# tvbgonesmd4led.net
KiCad netlist of a schematic drawn in EAGLE
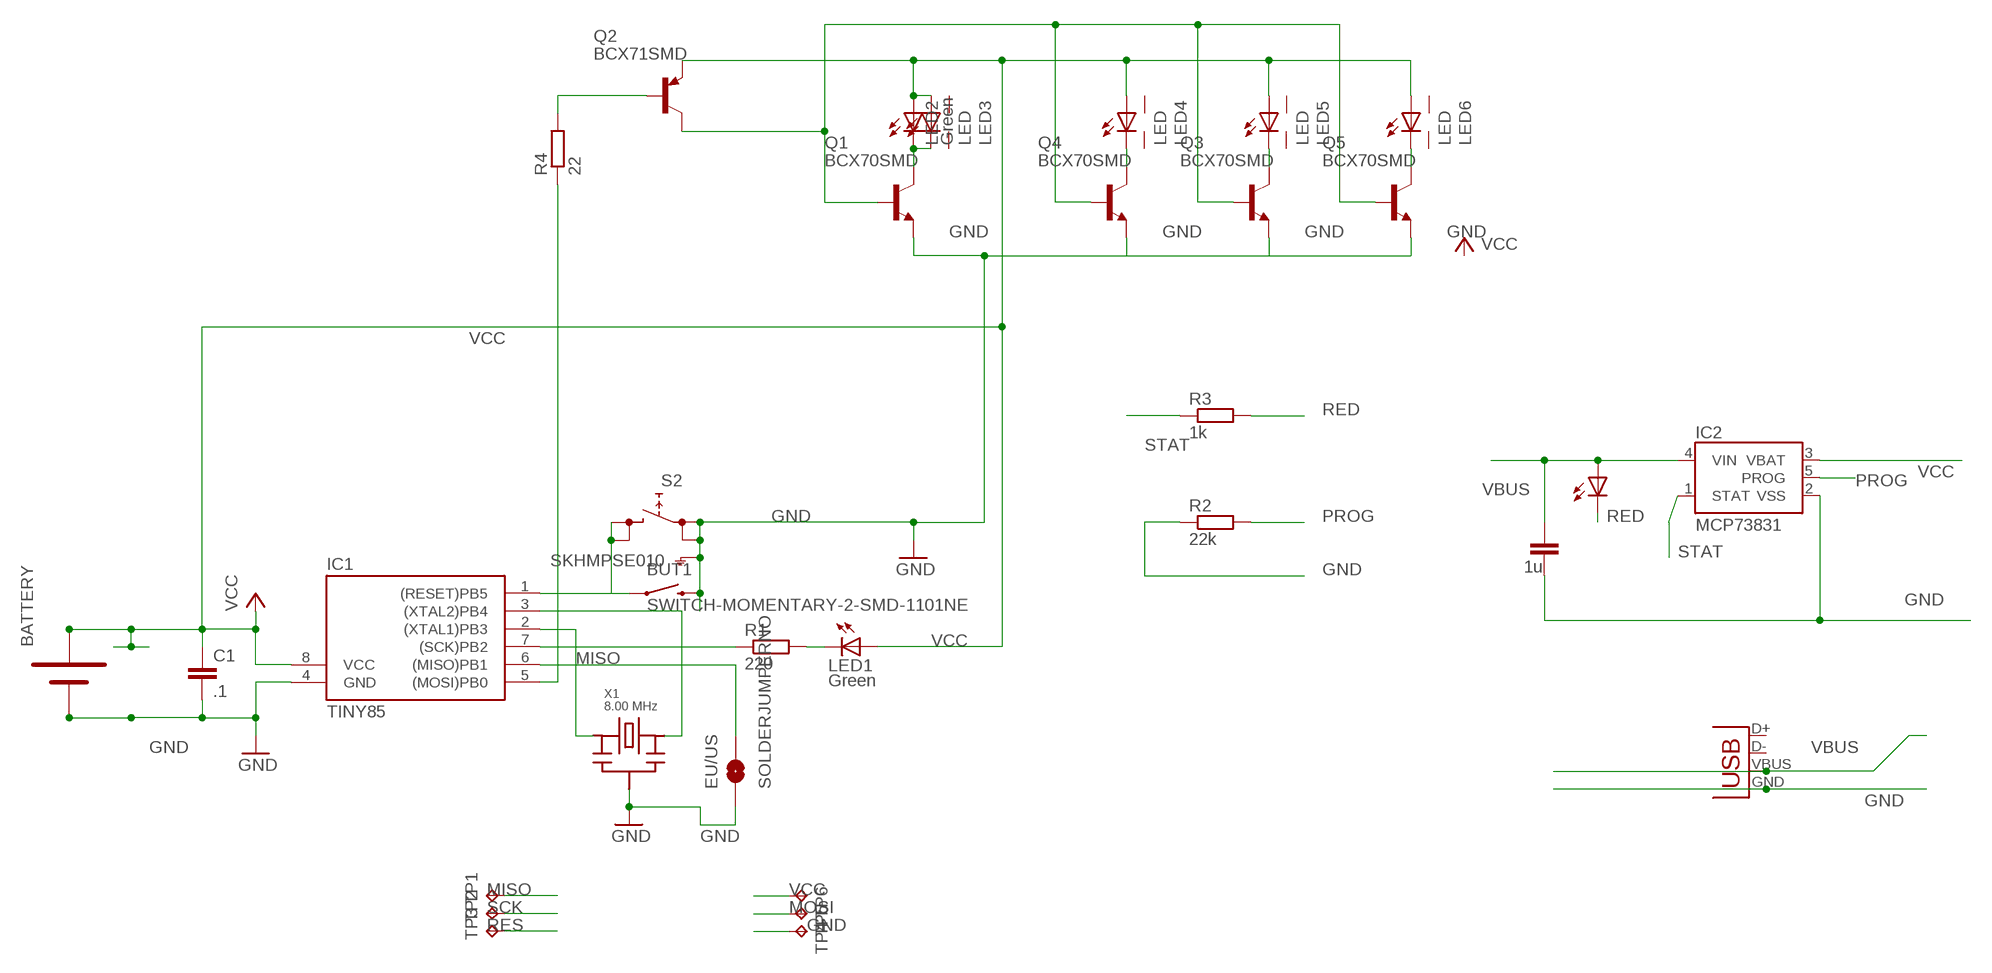
[diagram p0: schematic, sheet 1]

(export (version "E")
  (design (tool "Eeschema 10.0.6"))
  (components
    (comp (ref "BATTERY")
      (value "BATTERY-1XAA20MM")
      (footprint "eagle-import:BATTCOM_20MM_PTH")
      (libsource (lib "eagle-import") (part "BATTERY-1XAA20MM"))
    )
    (comp (ref "BUT1")
      (value "SWITCH-MOMENTARY-2-SMD-1101NE")
      (footprint "eagle-import:TACTILE-SWITCH-1101NE")
      (libsource (lib "eagle-import") (part "SWITCH-MOMENTARY-2-SMD-1101NE"))
    )
    (comp (ref "C1")
      (value ".1")
      (footprint "eagle-import:C0603")
      (libsource (lib "eagle-import") (part "C-EUC0603"))
    )
    (comp (ref "C2")
      (value "1u")
      (footprint "eagle-import:C0603")
      (libsource (lib "eagle-import") (part "resistor_C-EUC0603"))
    )
    (comp (ref "CHG")
      (value "0805")
      (footprint "eagle-import:CHIPLED_0603")
      (libsource (lib "eagle-import") (part "LEDCHIPLED_0603"))
    )
    (comp (ref "EU/US")
      (value "SOLDERJUMPERNO")
      (footprint "eagle-import:SJ_2S-NO")
      (libsource (lib "eagle-import") (part "SOLDERJUMPERNO"))
    )
    (comp (ref "IC1")
      (value "TINY85")
      (footprint "eagle-import:SOIC8")
      (libsource (lib "eagle-import") (part "TINY12S"))
    )
    (comp (ref "IC2")
      (value "MCP73831")
      (footprint "eagle-import:SOT23-5")
      (libsource (lib "eagle-import") (part "MCP73831"))
    )
    (comp (ref "LED1")
      (value "Green")
      (footprint "eagle-import:CHIPLED_0603")
      (libsource (lib "eagle-import") (part "LEDCHIPLED_0603"))
    )
    (comp (ref "LED2")
      (value "Green")
      (footprint "eagle-import:CHIPLED_0805")
      (libsource (lib "eagle-import") (part "LEDCHIPLED_0805"))
    )
    (comp (ref "LED3")
      (value "LED")
      (footprint "eagle-import:5MM-SIDE")
      (libsource (lib "eagle-import") (part "tvbgone_LED"))
    )
    (comp (ref "LED4")
      (value "LED")
      (footprint "eagle-import:5MM-SIDE")
      (libsource (lib "eagle-import") (part "tvbgone_LED"))
    )
    (comp (ref "LED5")
      (value "LED")
      (footprint "eagle-import:5MM-SIDE")
      (libsource (lib "eagle-import") (part "tvbgone_LED"))
    )
    (comp (ref "LED6")
      (value "LED")
      (footprint "eagle-import:5MM-SIDE")
      (libsource (lib "eagle-import") (part "tvbgone_LED"))
    )
    (comp (ref "Q1")
      (value "BCX70SMD")
      (footprint "eagle-import:SOT23")
      (libsource (lib "eagle-import") (part "BCX70SMD"))
    )
    (comp (ref "Q2")
      (value "BCX71SMD")
      (footprint "eagle-import:SOT23")
      (libsource (lib "eagle-import") (part "BCX71SMD"))
    )
    (comp (ref "Q3")
      (value "BCX70SMD")
      (footprint "eagle-import:SOT23")
      (libsource (lib "eagle-import") (part "BCX70SMD"))
    )
    (comp (ref "Q4")
      (value "BCX70SMD")
      (footprint "eagle-import:SOT23")
      (libsource (lib "eagle-import") (part "BCX70SMD"))
    )
    (comp (ref "Q5")
      (value "BCX70SMD")
      (footprint "eagle-import:SOT23")
      (libsource (lib "eagle-import") (part "BCX70SMD"))
    )
    (comp (ref "R1")
      (value "220")
      (footprint "eagle-import:R0603")
      (libsource (lib "eagle-import") (part "R-EU_R0603"))
    )
    (comp (ref "R2")
      (value "22k")
      (footprint "eagle-import:R0603")
      (libsource (lib "eagle-import") (part "R-EU_R0603"))
    )
    (comp (ref "R3")
      (value "1k")
      (footprint "eagle-import:R0603")
      (libsource (lib "eagle-import") (part "R-EU_R0603"))
    )
    (comp (ref "R4")
      (value "22")
      (footprint "eagle-import:R0603")
      (libsource (lib "eagle-import") (part "R-EU_R0603"))
    )
    (comp (ref "S2")
      (value "SKHMPSE010")
      (footprint "eagle-import:SKHMPXE010")
      (libsource (lib "eagle-import") (part "SKHMPE010S"))
    )
    (comp (ref "TP1")
      (value "TPB1,27")
      (footprint "eagle-import:B1,27")
      (libsource (lib "eagle-import") (part "TPB1,27"))
    )
    (comp (ref "TP2")
      (value "TPB1,27")
      (footprint "eagle-import:B1,27")
      (libsource (lib "eagle-import") (part "TPB1,27"))
    )
    (comp (ref "TP3")
      (value "TPB1,27")
      (footprint "eagle-import:B1,27")
      (libsource (lib "eagle-import") (part "TPB1,27"))
    )
    (comp (ref "TP4")
      (value "TPB1,27")
      (footprint "eagle-import:B1,27")
      (libsource (lib "eagle-import") (part "TPB1,27"))
    )
    (comp (ref "TP5")
      (value "TPB1,27")
      (footprint "eagle-import:B1,27")
      (libsource (lib "eagle-import") (part "TPB1,27"))
    )
    (comp (ref "TP6")
      (value "TPB1,27")
      (footprint "eagle-import:B1,27")
      (libsource (lib "eagle-import") (part "TPB1,27"))
    )
    (comp (ref "X1")
      (value "8.00 MHz")
      (footprint "eagle-import:AWSCR")
      (libsource (lib "eagle-import") (part "AWSCR-MT"))
    )
    (comp (ref "X6")
      (value "USB-MICROB")
      (footprint "eagle-import:USB-MICROB")
      (libsource (lib "eagle-import") (part "USB-MICROB"))
    )
  )
  (nets
    (net (code "1") (name "/MISO") (class "Default")
      (node (ref "EU/US") (pin "2") (pinfunction "2_2") (pintype "passive"))
      (node (ref "IC1") (pin "6") (pinfunction "(MISO)PB1_6") (pintype "bidirectional"))
      (node (ref "TP1") (pin "TP") (pinfunction "TP_TP") (pintype "input"))
    )
    (net (code "2") (name "/MOSI") (class "Default")
      (node (ref "IC1") (pin "5") (pinfunction "(MOSI)PB0_5") (pintype "bidirectional"))
      (node (ref "R4") (pin "1") (pinfunction "1_1") (pintype "passive"))
      (node (ref "TP5") (pin "TP") (pinfunction "TP_TP") (pintype "input"))
    )
    (net (code "3") (name "/PROG") (class "Default")
      (node (ref "IC2") (pin "5") (pinfunction "PROG_5") (pintype "input"))
      (node (ref "R2") (pin "2") (pinfunction "2_2") (pintype "passive"))
    )
    (net (code "4") (name "/RED") (class "Default")
      (node (ref "CHG") (pin "C") (pinfunction "C_C") (pintype "passive"))
      (node (ref "R3") (pin "2") (pinfunction "2_2") (pintype "passive"))
    )
    (net (code "5") (name "/RES") (class "Default")
      (node (ref "BUT1") (pin "P$1") (pinfunction "1_P$1") (pintype "passive"))
      (node (ref "IC1") (pin "1") (pinfunction "(RESET)PB5_1") (pintype "bidirectional"))
      (node (ref "S2") (pin "3") (pinfunction "2.1_3") (pintype "passive"))
      (node (ref "S2") (pin "4") (pinfunction "2.2_4") (pintype "passive"))
      (node (ref "TP3") (pin "TP") (pinfunction "TP_TP") (pintype "input"))
    )
    (net (code "6") (name "/SCK") (class "Default")
      (node (ref "IC1") (pin "7") (pinfunction "(SCK)PB2_7") (pintype "bidirectional"))
      (node (ref "R1") (pin "1") (pinfunction "1_1") (pintype "passive"))
      (node (ref "TP2") (pin "TP") (pinfunction "TP_TP") (pintype "input"))
    )
    (net (code "7") (name "/STAT") (class "Default")
      (node (ref "IC2") (pin "1") (pinfunction "STAT_1") (pintype "output"))
      (node (ref "R3") (pin "1") (pinfunction "1_1") (pintype "passive"))
    )
    (net (code "8") (name "/VBUS") (class "Default")
      (node (ref "C2") (pin "1") (pinfunction "1_1") (pintype "passive"))
      (node (ref "CHG") (pin "A") (pinfunction "A_A") (pintype "passive"))
      (node (ref "IC2") (pin "4") (pinfunction "VIN_4") (pintype "power_in"))
      (node (ref "X6") (pin "VBUS") (pinfunction "VBUS_VBUS") (pintype "bidirectional"))
    )
    (net (code "9") (name "GND") (class "Default")
      (node (ref "BATTERY") (pin "-") (pinfunction "-_-") (pintype "bidirectional"))
      (node (ref "BUT1") (pin "P$2") (pinfunction "2_P$2") (pintype "passive"))
      (node (ref "C1") (pin "2") (pinfunction "2_2") (pintype "passive"))
      (node (ref "C2") (pin "2") (pinfunction "2_2") (pintype "passive"))
      (node (ref "EU/US") (pin "1") (pinfunction "1_1") (pintype "passive"))
      (node (ref "IC1") (pin "4") (pinfunction "GND_4") (pintype "power_in"))
      (node (ref "IC2") (pin "2") (pinfunction "VSS_2") (pintype "power_in"))
      (node (ref "Q1") (pin "2") (pinfunction "E_2") (pintype "passive"))
      (node (ref "Q3") (pin "2") (pinfunction "E_2") (pintype "passive"))
      (node (ref "Q4") (pin "2") (pinfunction "E_2") (pintype "passive"))
      (node (ref "Q5") (pin "2") (pinfunction "E_2") (pintype "passive"))
      (node (ref "R2") (pin "1") (pinfunction "1_1") (pintype "passive"))
      (node (ref "S2") (pin "1") (pinfunction "1.1_1") (pintype "passive"))
      (node (ref "S2") (pin "2") (pinfunction "1.2_2") (pintype "passive"))
      (node (ref "S2") (pin "5") (pinfunction "SH_5") (pintype "passive"))
      (node (ref "TP4") (pin "TP") (pinfunction "TP_TP") (pintype "input"))
      (node (ref "X1") (pin "P$2") (pinfunction "GND_P$2") (pintype "passive"))
      (node (ref "X6") (pin "GND") (pinfunction "GND_GND") (pintype "bidirectional"))
    )
    (net (code "10") (name "Net-(IC1-(XTAL1)PB3)") (class "Default")
      (node (ref "IC1") (pin "2") (pinfunction "(XTAL1)PB3_2") (pintype "bidirectional"))
      (node (ref "X1") (pin "P$1") (pinfunction "P$1_P$1") (pintype "passive"))
    )
    (net (code "11") (name "Net-(IC1-(XTAL2)PB4)") (class "Default")
      (node (ref "IC1") (pin "3") (pinfunction "(XTAL2)PB4_3") (pintype "bidirectional"))
      (node (ref "X1") (pin "P$3") (pinfunction "P$2_P$3") (pintype "passive"))
    )
    (net (code "12") (name "Net-(LED1-PadC)") (class "Default")
      (node (ref "LED1") (pin "C") (pinfunction "C_C") (pintype "passive"))
      (node (ref "R1") (pin "2") (pinfunction "2_2") (pintype "passive"))
    )
    (net (code "13") (name "Net-(LED3-C)") (class "Default")
      (node (ref "LED2") (pin "C") (pinfunction "C_C") (pintype "passive"))
      (node (ref "LED3") (pin "K") (pinfunction "C_K") (pintype "passive"))
      (node (ref "Q1") (pin "3") (pinfunction "C_3") (pintype "passive"))
    )
    (net (code "14") (name "Net-(LED4-C)") (class "Default")
      (node (ref "LED4") (pin "K") (pinfunction "C_K") (pintype "passive"))
      (node (ref "Q4") (pin "3") (pinfunction "C_3") (pintype "passive"))
    )
    (net (code "15") (name "Net-(LED5-C)") (class "Default")
      (node (ref "LED5") (pin "K") (pinfunction "C_K") (pintype "passive"))
      (node (ref "Q3") (pin "3") (pinfunction "C_3") (pintype "passive"))
    )
    (net (code "16") (name "Net-(LED6-C)") (class "Default")
      (node (ref "LED6") (pin "K") (pinfunction "C_K") (pintype "passive"))
      (node (ref "Q5") (pin "3") (pinfunction "C_3") (pintype "passive"))
    )
    (net (code "17") (name "Net-(Q1-B)") (class "Default")
      (node (ref "Q1") (pin "1") (pinfunction "B_1") (pintype "passive"))
      (node (ref "Q2") (pin "3") (pinfunction "C_3") (pintype "passive"))
      (node (ref "Q3") (pin "1") (pinfunction "B_1") (pintype "passive"))
      (node (ref "Q4") (pin "1") (pinfunction "B_1") (pintype "passive"))
      (node (ref "Q5") (pin "1") (pinfunction "B_1") (pintype "passive"))
    )
    (net (code "18") (name "Net-(Q2-B)") (class "Default")
      (node (ref "Q2") (pin "1") (pinfunction "B_1") (pintype "passive"))
      (node (ref "R4") (pin "2") (pinfunction "2_2") (pintype "passive"))
    )
    (net (code "19") (name "VCC") (class "Default")
      (node (ref "BATTERY") (pin "+") (pinfunction "+_+") (pintype "bidirectional"))
      (node (ref "C1") (pin "1") (pinfunction "1_1") (pintype "passive"))
      (node (ref "IC1") (pin "8") (pinfunction "VCC_8") (pintype "power_in"))
      (node (ref "IC2") (pin "3") (pinfunction "VBAT_3") (pintype "power_in"))
      (node (ref "LED1") (pin "A") (pinfunction "A_A") (pintype "passive"))
      (node (ref "LED2") (pin "A") (pinfunction "A_A") (pintype "passive"))
      (node (ref "LED3") (pin "A") (pinfunction "A_A") (pintype "passive"))
      (node (ref "LED4") (pin "A") (pinfunction "A_A") (pintype "passive"))
      (node (ref "LED5") (pin "A") (pinfunction "A_A") (pintype "passive"))
      (node (ref "LED6") (pin "A") (pinfunction "A_A") (pintype "passive"))
      (node (ref "Q2") (pin "2") (pinfunction "E_2") (pintype "passive"))
      (node (ref "TP6") (pin "TP") (pinfunction "TP_TP") (pintype "input"))
    )
    (net (code "20") (name "unconnected-(LED3-A1-PadA2)") (class "Default")
      (node (ref "LED3") (pin "A2") (pinfunction "A1_A2") (pintype "passive"))
    )
    (net (code "21") (name "unconnected-(LED3-C1-PadK2)") (class "Default")
      (node (ref "LED3") (pin "K2") (pinfunction "C1_K2") (pintype "passive"))
    )
    (net (code "22") (name "unconnected-(LED4-A1-PadA2)") (class "Default")
      (node (ref "LED4") (pin "A2") (pinfunction "A1_A2") (pintype "passive"))
    )
    (net (code "23") (name "unconnected-(LED4-C1-PadK2)") (class "Default")
      (node (ref "LED4") (pin "K2") (pinfunction "C1_K2") (pintype "passive"))
    )
    (net (code "24") (name "unconnected-(LED5-A1-PadA2)") (class "Default")
      (node (ref "LED5") (pin "A2") (pinfunction "A1_A2") (pintype "passive"))
    )
    (net (code "25") (name "unconnected-(LED5-C1-PadK2)") (class "Default")
      (node (ref "LED5") (pin "K2") (pinfunction "C1_K2") (pintype "passive"))
    )
    (net (code "26") (name "unconnected-(LED6-A1-PadA2)") (class "Default")
      (node (ref "LED6") (pin "A2") (pinfunction "A1_A2") (pintype "passive"))
    )
    (net (code "27") (name "unconnected-(LED6-C1-PadK2)") (class "Default")
      (node (ref "LED6") (pin "K2") (pinfunction "C1_K2") (pintype "passive"))
    )
    (net (code "28") (name "unconnected-(X6-PadD+)") (class "Default")
      (node (ref "X6") (pin "D+") (pinfunction "D+_D+") (pintype "bidirectional"))
    )
    (net (code "29") (name "unconnected-(X6-PadD-)") (class "Default")
      (node (ref "X6") (pin "D-") (pinfunction "D-_D-") (pintype "bidirectional"))
    )
  )
)
